# rapidshark-half-assed-half-h-bridge-mk-1.net
KiCad netlist of a schematic drawn in EAGLE
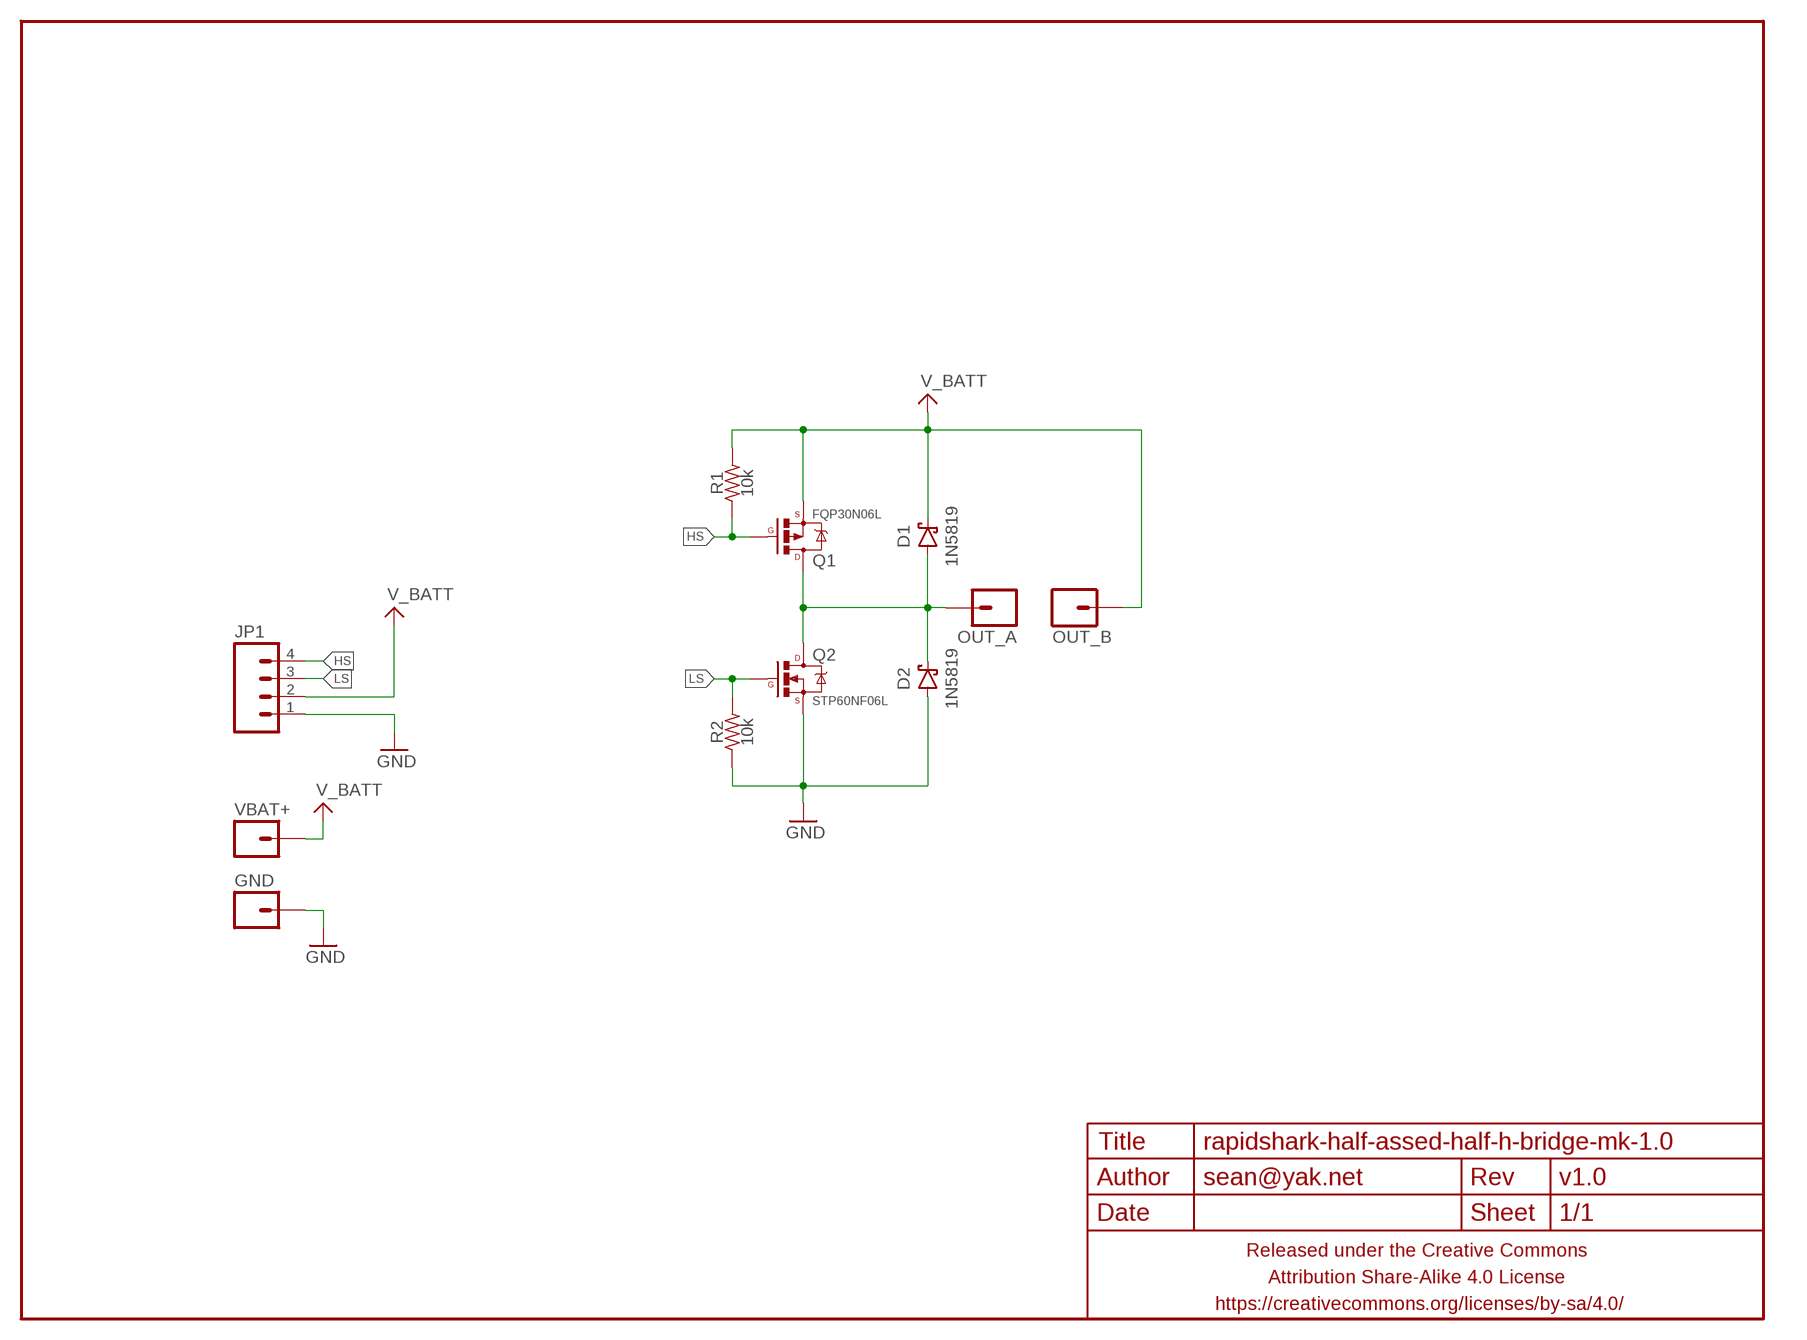
[diagram p0: schematic, sheet 1]

(export (version "E")
  (design (tool "Eeschema 10.0.6"))
  (components
    (comp (ref "D1")
      (value "1N5819")
      (footprint "eagle-import:DIODE-SCHOTTKY-10.16MM")
      (libsource (lib "eagle-import") (part "DIODE-SCHOTTKYPTH-10.16MM"))
    )
    (comp (ref "D2")
      (value "1N5819")
      (footprint "eagle-import:DIODE-SCHOTTKY-10.16MM")
      (libsource (lib "eagle-import") (part "DIODE-SCHOTTKYPTH-10.16MM"))
    )
    (comp (ref "FRAME1")
      (value "FRAME-LETTERNO_PACKAGE")
      (footprint "eagle-import:DUMMY")
      (fields (field (name "DESIGNER") "sean@yak.net") (field (name "VERSION") "v1.0"))
      (libsource (lib "eagle-import") (part "FRAME-LETTERNO_PACKAGE"))
    )
    (comp (ref "GND")
      (value "M0112AWG")
      (footprint "eagle-import:1X01-12AWG")
      (libsource (lib "eagle-import") (part "M0112AWG"))
    )
    (comp (ref "JP1")
      (value "M04PTH")
      (footprint "eagle-import:1X04-PTH-VERT")
      (libsource (lib "eagle-import") (part "M04PTH"))
    )
    (comp (ref "OUT_A")
      (value "M0112AWG")
      (footprint "eagle-import:1X01-12AWG")
      (libsource (lib "eagle-import") (part "M0112AWG"))
    )
    (comp (ref "OUT_B")
      (value "M0112AWG")
      (footprint "eagle-import:1X01-12AWG")
      (libsource (lib "eagle-import") (part "M0112AWG"))
    )
    (comp (ref "Q1")
      (value "FQP30N06L")
      (footprint "eagle-import:TO220-THERMPAD")
      (libsource (lib "eagle-import") (part "MOSFET-PCHANNELTO-220-THERMPAD"))
    )
    (comp (ref "Q2")
      (value "STP60NF06L")
      (footprint "eagle-import:TO220-THERMPAD")
      (libsource (lib "eagle-import") (part "MOSFET-NCHANNELTO-220"))
    )
    (comp (ref "R1")
      (value "10k")
      (footprint "eagle-import:RESISTOR-AXIAL-PTH-5.08MM")
      (libsource (lib "eagle-import") (part "RESISTORPTH-AXIAL-5.08MM"))
    )
    (comp (ref "R2")
      (value "10k")
      (footprint "eagle-import:RESISTOR-AXIAL-PTH-5.08MM")
      (libsource (lib "eagle-import") (part "RESISTORPTH-AXIAL-5.08MM"))
    )
    (comp (ref "VBAT+")
      (value "M0112AWG")
      (footprint "eagle-import:1X01-12AWG")
      (libsource (lib "eagle-import") (part "M0112AWG"))
    )
  )
  (nets
    (net (code "1") (name "GND") (class "Default")
      (node (ref "D2") (pin "A") (pinfunction "A_A") (pintype "passive"))
      (node (ref "GND") (pin "1") (pinfunction "1_1") (pintype "passive"))
      (node (ref "JP1") (pin "1") (pinfunction "1_1") (pintype "passive"))
      (node (ref "Q2") (pin "3") (pinfunction "S_3") (pintype "passive"))
      (node (ref "R2") (pin "P$1") (pinfunction "1_P$1") (pintype "passive"))
    )
    (net (code "2") (name "HS") (class "Default")
      (node (ref "JP1") (pin "4") (pinfunction "4_4") (pintype "passive"))
      (node (ref "Q1") (pin "1") (pinfunction "G_1") (pintype "passive"))
      (node (ref "R1") (pin "P$1") (pinfunction "1_P$1") (pintype "passive"))
    )
    (net (code "3") (name "LS") (class "Default")
      (node (ref "JP1") (pin "3") (pinfunction "3_3") (pintype "passive"))
      (node (ref "Q2") (pin "1") (pinfunction "G_1") (pintype "passive"))
      (node (ref "R2") (pin "P$2") (pinfunction "2_P$2") (pintype "passive"))
    )
    (net (code "4") (name "Net-(D1-PadA)") (class "Default")
      (node (ref "D1") (pin "A") (pinfunction "A_A") (pintype "passive"))
      (node (ref "D2") (pin "C") (pinfunction "C_C") (pintype "passive"))
      (node (ref "OUT_A") (pin "1") (pinfunction "1_1") (pintype "passive"))
      (node (ref "Q1") (pin "2@1") (pinfunction "D_2@1") (pintype "passive"))
      (node (ref "Q1") (pin "2@2") (pinfunction "D_2@2") (pintype "passive"))
      (node (ref "Q2") (pin "2@1") (pinfunction "D_2@1") (pintype "passive"))
      (node (ref "Q2") (pin "2@2") (pinfunction "D_2@2") (pintype "passive"))
    )
    (net (code "5") (name "V_BATT") (class "Default")
      (node (ref "D1") (pin "C") (pinfunction "C_C") (pintype "passive"))
      (node (ref "JP1") (pin "2") (pinfunction "2_2") (pintype "passive"))
      (node (ref "OUT_B") (pin "1") (pinfunction "1_1") (pintype "passive"))
      (node (ref "Q1") (pin "3") (pinfunction "S_3") (pintype "passive"))
      (node (ref "R1") (pin "P$2") (pinfunction "2_P$2") (pintype "passive"))
      (node (ref "VBAT+") (pin "1") (pinfunction "1_1") (pintype "passive"))
    )
  )
)
